# bracelet_go-safe.net
KiCad netlist of a schematic drawn in EAGLE
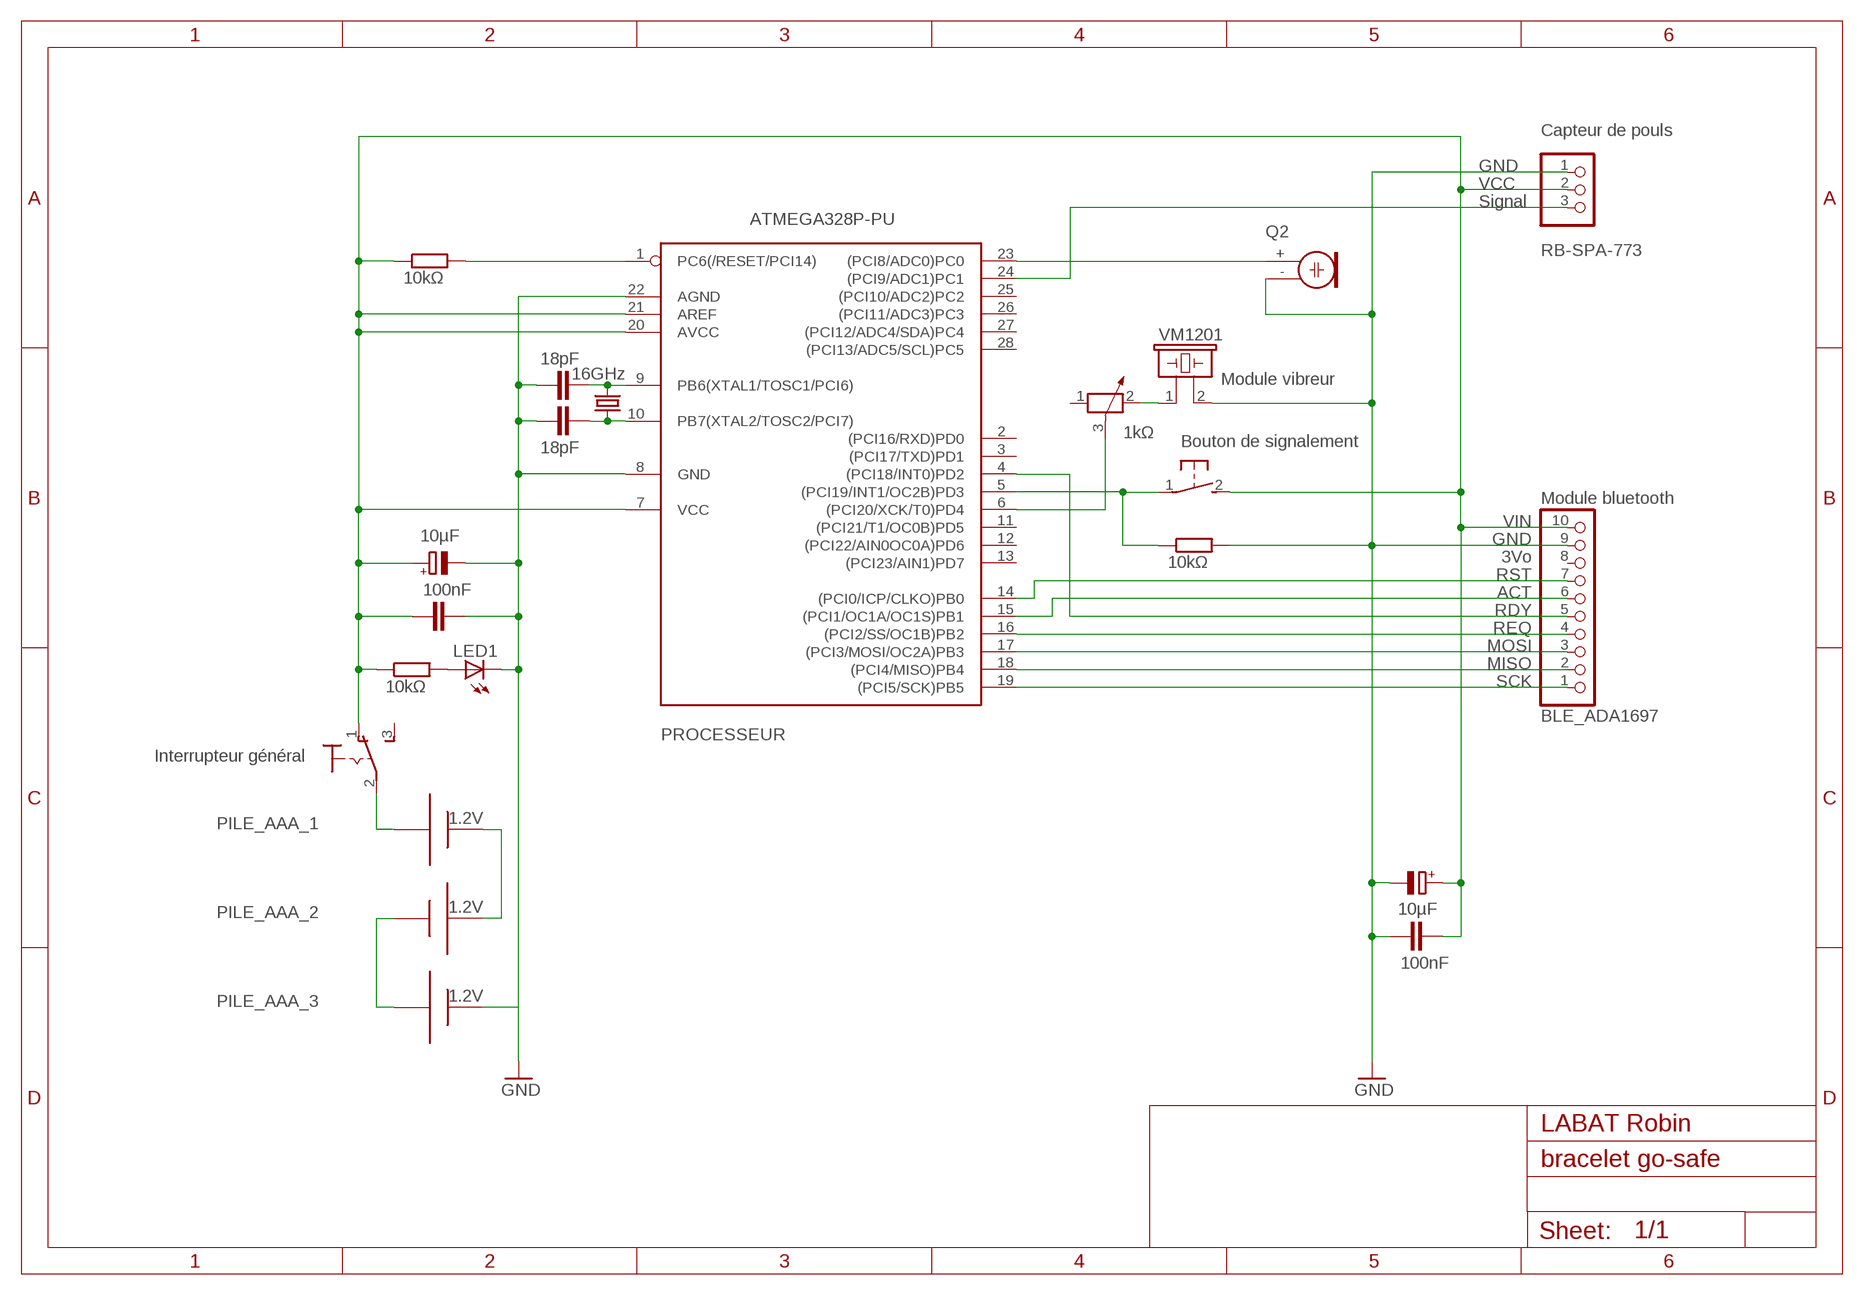
[diagram p0: schematic, sheet 1]

(export (version "E")
  (design (tool "Eeschema 10.0.6"))
  (components
    (comp (ref "BLE_ADA1697")
      (value "Module bluetooth")
      (footprint "eagle-import:1X10-BIG")
      (fields
        (field (name "PIN1") "SCK")
        (field (name "PIN10") "VIN")
        (field (name "PIN2") "MISO")
        (field (name "PIN3") "MOSI")
        (field (name "PIN4") "REQ")
        (field (name "PIN5") "RDY")
        (field (name "PIN6") "ACT")
        (field (name "PIN7") "RST")
        (field (name "PIN8") "3Vo")
        (field (name "PIN9") "GND")
      )
      (libsource (lib "eagle-import") (part "PINHD-1X10"))
    )
    (comp (ref "C1")
      (value "18pF")
      (footprint "eagle-import:C025-024X044")
      (libsource (lib "eagle-import") (part "C-EU025-024X044"))
    )
    (comp (ref "C2")
      (value "18pF")
      (footprint "eagle-import:C025-024X044")
      (libsource (lib "eagle-import") (part "C-EU025-024X044"))
    )
    (comp (ref "C3")
      (value "100nF")
      (footprint "eagle-import:C025-024X044")
      (libsource (lib "eagle-import") (part "C-EU025-024X044"))
    )
    (comp (ref "C4")
      (value "100nF")
      (footprint "eagle-import:C025-024X044")
      (libsource (lib "eagle-import") (part "C-EU025-024X044"))
    )
    (comp (ref "C5")
      (value "10µF")
      (footprint "eagle-import:085CS_1AR")
      (libsource (lib "eagle-import") (part "CPOL-EU085CS-1AR"))
    )
    (comp (ref "C6")
      (value "10µF")
      (footprint "eagle-import:085CS_1AR")
      (libsource (lib "eagle-import") (part "CPOL-EU085CS-1AR"))
    )
    (comp (ref "FRAME1")
      (value "A4L-LOC")
      (footprint "eagle-import:A4L-LOC")
      (libsource (lib "eagle-import") (part "A4L-LOC"))
    )
    (comp (ref "LED1")
      (value "LED")
      (footprint "eagle-import:SMARTLED-TTW")
      (libsource (lib "eagle-import") (part "LED"))
    )
    (comp (ref "PILE_AAA_1")
      (value "AAA")
      (footprint "eagle-import:12BH412")
      (fields (field (name "TENSION") "1.2V"))
      (libsource (lib "eagle-import") (part "AAA"))
    )
    (comp (ref "PILE_AAA_2")
      (value "AAA")
      (footprint "eagle-import:12BH412")
      (fields (field (name "TENSION") "1.2V"))
      (libsource (lib "eagle-import") (part "AAA"))
    )
    (comp (ref "PILE_AAA_3")
      (value "AAA")
      (footprint "eagle-import:12BH412")
      (fields (field (name "TENSION") "1.2V"))
      (libsource (lib "eagle-import") (part "AAA"))
    )
    (comp (ref "PROCESSEUR")
      (value "ATMEGA328P-PU")
      (footprint "eagle-import:DIL28-3")
      (libsource (lib "eagle-import") (part "ATMEGA168PV-10"))
    )
    (comp (ref "Q1")
      (value "16GHz")
      (footprint "eagle-import:86SMX")
      (libsource (lib "eagle-import") (part "CRYSTAL68SMX"))
    )
    (comp (ref "Q2")
      (value "ELECTRET")
      (footprint "eagle-import:9.7ELECTRET")
      (libsource (lib "eagle-import") (part "ELECTRET"))
    )
    (comp (ref "R1")
      (value "1kΩ")
      (footprint "eagle-import:PT-10")
      (libsource (lib "eagle-import") (part "POTENTIOMETER_PT-10"))
    )
    (comp (ref "R2")
      (value "10kΩ")
      (footprint "eagle-import:0204V")
      (libsource (lib "eagle-import") (part "R-EU_0204/2V"))
    )
    (comp (ref "R3")
      (value "10kΩ")
      (footprint "eagle-import:0204V")
      (libsource (lib "eagle-import") (part "R-EU_0204/2V"))
    )
    (comp (ref "R4")
      (value "10kΩ")
      (footprint "eagle-import:0204V")
      (libsource (lib "eagle-import") (part "R-EU_0204/2V"))
    )
    (comp (ref "RB-SPA-773")
      (value "Capteur de pouls")
      (footprint "eagle-import:1X03")
      (fields (field (name "PIN1") "GND") (field (name "PIN2") "VCC") (field (name "PIN3") "Signal"))
      (libsource (lib "eagle-import") (part "PINHD-1X3"))
    )
    (comp (ref "S2")
      (value "Bouton de signalement")
      (footprint "eagle-import:B3F-31XX")
      (fields (field (name "MPN") "B3F-3100"))
      (libsource (lib "eagle-import") (part "31-XX"))
    )
    (comp (ref "S3")
      (value "Interrupteur général")
      (footprint "eagle-import:320-916")
      (libsource (lib "eagle-import") (part "320-916"))
    )
    (comp (ref "VM1201")
      (value "Module vibreur")
      (footprint "eagle-import:B_C14S")
      (libsource (lib "eagle-import") (part "B/C14S"))
    )
  )
  (nets
    (net (code "1") (name "GND") (class "Default")
      (node (ref "BLE_ADA1697") (pin "9") (pinfunction "9_9") (pintype "passive"))
      (node (ref "C1") (pin "1") (pinfunction "1_1") (pintype "passive"))
      (node (ref "C2") (pin "1") (pinfunction "1_1") (pintype "passive"))
      (node (ref "C3") (pin "2") (pinfunction "2_2") (pintype "passive"))
      (node (ref "C4") (pin "2") (pinfunction "2_2") (pintype "passive"))
      (node (ref "C5") (pin "-") (pinfunction "-_-") (pintype "passive"))
      (node (ref "C6") (pin "-") (pinfunction "-_-") (pintype "passive"))
      (node (ref "LED1") (pin "C@1") (pinfunction "C_C@1") (pintype "passive"))
      (node (ref "PILE_AAA_3") (pin "+") (pinfunction "+_+") (pintype "bidirectional"))
      (node (ref "PROCESSEUR") (pin "22") (pinfunction "AGND_22") (pintype "bidirectional"))
      (node (ref "PROCESSEUR") (pin "8") (pinfunction "GND_8") (pintype "bidirectional"))
      (node (ref "Q2") (pin "-") (pinfunction "1_-") (pintype "passive"))
      (node (ref "R2") (pin "2") (pinfunction "2_2") (pintype "passive"))
      (node (ref "RB-SPA-773") (pin "1") (pinfunction "1_1") (pintype "passive"))
      (node (ref "VM1201") (pin "2") (pinfunction "2_2") (pintype "passive"))
    )
    (net (code "2") (name "Net-(LED1-A)") (class "Default")
      (node (ref "LED1") (pin "A@1") (pinfunction "A_A@1") (pintype "passive"))
      (node (ref "R3") (pin "2") (pinfunction "2_2") (pintype "passive"))
    )
    (net (code "3") (name "Net-(PILE_AAA_1-Pad+)") (class "Default")
      (node (ref "PILE_AAA_1") (pin "+") (pinfunction "+_+") (pintype "bidirectional"))
      (node (ref "PILE_AAA_2") (pin "-") (pinfunction "-_-") (pintype "bidirectional"))
    )
    (net (code "4") (name "Net-(PILE_AAA_2-Pad+)") (class "Default")
      (node (ref "PILE_AAA_2") (pin "+") (pinfunction "+_+") (pintype "bidirectional"))
      (node (ref "PILE_AAA_3") (pin "-") (pinfunction "-_-") (pintype "bidirectional"))
    )
    (net (code "5") (name "Net-(PROCESSEUR-(PCI0{slash}ICP{slash}CLKO)PB0)") (class "Default")
      (node (ref "BLE_ADA1697") (pin "7") (pinfunction "7_7") (pintype "passive"))
      (node (ref "PROCESSEUR") (pin "14") (pinfunction "(PCI0/ICP/CLKO)PB0_14") (pintype "bidirectional"))
    )
    (net (code "6") (name "Net-(PROCESSEUR-(PCI1{slash}OC1A{slash}OC1S)PB1)") (class "Default")
      (node (ref "BLE_ADA1697") (pin "6") (pinfunction "6_6") (pintype "passive"))
      (node (ref "PROCESSEUR") (pin "15") (pinfunction "(PCI1/OC1A/OC1S)PB1_15") (pintype "bidirectional"))
    )
    (net (code "7") (name "Net-(PROCESSEUR-(PCI2{slash}SS{slash}OC1B)PB2)") (class "Default")
      (node (ref "BLE_ADA1697") (pin "4") (pinfunction "4_4") (pintype "passive"))
      (node (ref "PROCESSEUR") (pin "16") (pinfunction "(PCI2/SS/OC1B)PB2_16") (pintype "bidirectional"))
    )
    (net (code "8") (name "Net-(PROCESSEUR-(PCI3{slash}MOSI{slash}OC2A)PB3)") (class "Default")
      (node (ref "BLE_ADA1697") (pin "3") (pinfunction "3_3") (pintype "passive"))
      (node (ref "PROCESSEUR") (pin "17") (pinfunction "(PCI3/MOSI/OC2A)PB3_17") (pintype "bidirectional"))
    )
    (net (code "9") (name "Net-(PROCESSEUR-(PCI4{slash}MISO)PB4)") (class "Default")
      (node (ref "BLE_ADA1697") (pin "2") (pinfunction "2_2") (pintype "passive"))
      (node (ref "PROCESSEUR") (pin "18") (pinfunction "(PCI4/MISO)PB4_18") (pintype "bidirectional"))
    )
    (net (code "10") (name "Net-(PROCESSEUR-(PCI5{slash}SCK)PB5)") (class "Default")
      (node (ref "BLE_ADA1697") (pin "1") (pinfunction "1_1") (pintype "passive"))
      (node (ref "PROCESSEUR") (pin "19") (pinfunction "(PCI5/SCK)PB5_19") (pintype "bidirectional"))
    )
    (net (code "11") (name "Net-(PROCESSEUR-(PCI8{slash}ADC0)PC0)") (class "Default")
      (node (ref "PROCESSEUR") (pin "23") (pinfunction "(PCI8/ADC0)PC0_23") (pintype "bidirectional"))
      (node (ref "Q2") (pin "+") (pinfunction "2_+") (pintype "passive"))
    )
    (net (code "12") (name "Net-(PROCESSEUR-(PCI9{slash}ADC1)PC1)") (class "Default")
      (node (ref "PROCESSEUR") (pin "24") (pinfunction "(PCI9/ADC1)PC1_24") (pintype "bidirectional"))
      (node (ref "RB-SPA-773") (pin "3") (pinfunction "3_3") (pintype "passive"))
    )
    (net (code "13") (name "Net-(PROCESSEUR-(PCI18{slash}INT0)PD2)") (class "Default")
      (node (ref "BLE_ADA1697") (pin "5") (pinfunction "5_5") (pintype "passive"))
      (node (ref "PROCESSEUR") (pin "4") (pinfunction "(PCI18/INT0)PD2_4") (pintype "bidirectional"))
    )
    (net (code "14") (name "Net-(PROCESSEUR-(PCI19{slash}INT1{slash}OC2B)PD3)") (class "Default")
      (node (ref "PROCESSEUR") (pin "5") (pinfunction "(PCI19/INT1/OC2B)PD3_5") (pintype "bidirectional"))
      (node (ref "R2") (pin "1") (pinfunction "1_1") (pintype "passive"))
      (node (ref "S2") (pin "1") (pinfunction "P_1") (pintype "passive"))
    )
    (net (code "15") (name "Net-(PROCESSEUR-(PCI20{slash}XCK{slash}T0)PD4)") (class "Default")
      (node (ref "PROCESSEUR") (pin "6") (pinfunction "(PCI20/XCK/T0)PD4_6") (pintype "bidirectional"))
      (node (ref "R1") (pin "3") (pinfunction "3_3") (pintype "passive"))
    )
    (net (code "16") (name "Net-(PROCESSEUR-AREF)") (class "Default")
      (node (ref "BLE_ADA1697") (pin "10") (pinfunction "10_10") (pintype "passive"))
      (node (ref "C3") (pin "1") (pinfunction "1_1") (pintype "passive"))
      (node (ref "C4") (pin "1") (pinfunction "1_1") (pintype "passive"))
      (node (ref "C5") (pin "+") (pinfunction "+_+") (pintype "passive"))
      (node (ref "C6") (pin "+") (pinfunction "+_+") (pintype "passive"))
      (node (ref "PROCESSEUR") (pin "20") (pinfunction "AVCC_20") (pintype "bidirectional"))
      (node (ref "PROCESSEUR") (pin "21") (pinfunction "AREF_21") (pintype "bidirectional"))
      (node (ref "PROCESSEUR") (pin "7") (pinfunction "VCC_7") (pintype "bidirectional"))
      (node (ref "R3") (pin "1") (pinfunction "1_1") (pintype "passive"))
      (node (ref "R4") (pin "1") (pinfunction "1_1") (pintype "passive"))
      (node (ref "RB-SPA-773") (pin "2") (pinfunction "2_2") (pintype "passive"))
      (node (ref "S2") (pin "2") (pinfunction "S_2") (pintype "passive"))
      (node (ref "S3") (pin "1") (pinfunction "O_1") (pintype "passive"))
    )
    (net (code "17") (name "Net-(PROCESSEUR-PB6(XTAL1{slash}TOSC1{slash}PCI6))") (class "Default")
      (node (ref "C1") (pin "2") (pinfunction "2_2") (pintype "passive"))
      (node (ref "PROCESSEUR") (pin "9") (pinfunction "PB6(XTAL1/TOSC1/PCI6)_9") (pintype "bidirectional"))
      (node (ref "Q1") (pin "4") (pinfunction "2_4") (pintype "passive"))
    )
    (net (code "18") (name "Net-(PROCESSEUR-PB7(XTAL2{slash}TOSC2{slash}PCI7))") (class "Default")
      (node (ref "C2") (pin "2") (pinfunction "2_2") (pintype "passive"))
      (node (ref "PROCESSEUR") (pin "10") (pinfunction "PB7(XTAL2/TOSC2/PCI7)_10") (pintype "bidirectional"))
      (node (ref "Q1") (pin "1") (pinfunction "1_1") (pintype "passive"))
    )
    (net (code "19") (name "Net-(PROCESSEUR-PC6({slash}RESET{slash}PCI14))") (class "Default")
      (node (ref "PROCESSEUR") (pin "1") (pinfunction "PC6(/RESET/PCI14)_1") (pintype "bidirectional"))
      (node (ref "R4") (pin "2") (pinfunction "2_2") (pintype "passive"))
    )
    (net (code "20") (name "Net-(R1-Pad2)") (class "Default")
      (node (ref "R1") (pin "2") (pinfunction "2_2") (pintype "passive"))
      (node (ref "VM1201") (pin "1") (pinfunction "1_1") (pintype "passive"))
    )
    (net (code "21") (name "Net-(S3-P)") (class "Default")
      (node (ref "PILE_AAA_1") (pin "-") (pinfunction "-_-") (pintype "bidirectional"))
      (node (ref "S3") (pin "2") (pinfunction "P_2") (pintype "passive"))
    )
    (net (code "22") (name "unconnected-(BLE_ADA1697-Pad8)") (class "Default")
      (node (ref "BLE_ADA1697") (pin "8") (pinfunction "8_8") (pintype "passive"))
    )
    (net (code "23") (name "unconnected-(PROCESSEUR-(PCI10{slash}ADC2)PC2-Pad25)") (class "Default")
      (node (ref "PROCESSEUR") (pin "25") (pinfunction "(PCI10/ADC2)PC2_25") (pintype "bidirectional"))
    )
    (net (code "24") (name "unconnected-(PROCESSEUR-(PCI11{slash}ADC3)PC3-Pad26)") (class "Default")
      (node (ref "PROCESSEUR") (pin "26") (pinfunction "(PCI11/ADC3)PC3_26") (pintype "bidirectional"))
    )
    (net (code "25") (name "unconnected-(PROCESSEUR-(PCI12{slash}ADC4{slash}SDA)PC4-Pad27)") (class "Default")
      (node (ref "PROCESSEUR") (pin "27") (pinfunction "(PCI12/ADC4/SDA)PC4_27") (pintype "bidirectional"))
    )
    (net (code "26") (name "unconnected-(PROCESSEUR-(PCI13{slash}ADC5{slash}SCL)PC5-Pad28)") (class "Default")
      (node (ref "PROCESSEUR") (pin "28") (pinfunction "(PCI13/ADC5/SCL)PC5_28") (pintype "bidirectional"))
    )
    (net (code "27") (name "unconnected-(PROCESSEUR-(PCI16{slash}RXD)PD0-Pad2)") (class "Default")
      (node (ref "PROCESSEUR") (pin "2") (pinfunction "(PCI16/RXD)PD0_2") (pintype "bidirectional"))
    )
    (net (code "28") (name "unconnected-(PROCESSEUR-(PCI17{slash}TXD)PD1-Pad3)") (class "Default")
      (node (ref "PROCESSEUR") (pin "3") (pinfunction "(PCI17/TXD)PD1_3") (pintype "bidirectional"))
    )
    (net (code "29") (name "unconnected-(PROCESSEUR-(PCI21{slash}T1{slash}OC0B)PD5-Pad11)") (class "Default")
      (node (ref "PROCESSEUR") (pin "11") (pinfunction "(PCI21/T1/OC0B)PD5_11") (pintype "bidirectional"))
    )
    (net (code "30") (name "unconnected-(PROCESSEUR-(PCI22{slash}AIN0OC0A)PD6-Pad12)") (class "Default")
      (node (ref "PROCESSEUR") (pin "12") (pinfunction "(PCI22/AIN0OC0A)PD6_12") (pintype "bidirectional"))
    )
    (net (code "31") (name "unconnected-(PROCESSEUR-(PCI23{slash}AIN1)PD7-Pad13)") (class "Default")
      (node (ref "PROCESSEUR") (pin "13") (pinfunction "(PCI23/AIN1)PD7_13") (pintype "bidirectional"))
    )
    (net (code "32") (name "unconnected-(R1-Pad1)") (class "Default")
      (node (ref "R1") (pin "1") (pinfunction "1_1") (pintype "passive"))
    )
    (net (code "33") (name "unconnected-(S3-S-Pad3)") (class "Default")
      (node (ref "S3") (pin "3") (pinfunction "S_3") (pintype "passive"))
    )
  )
)
